# clock-converter.net
KiCad netlist of a schematic drawn in EAGLE
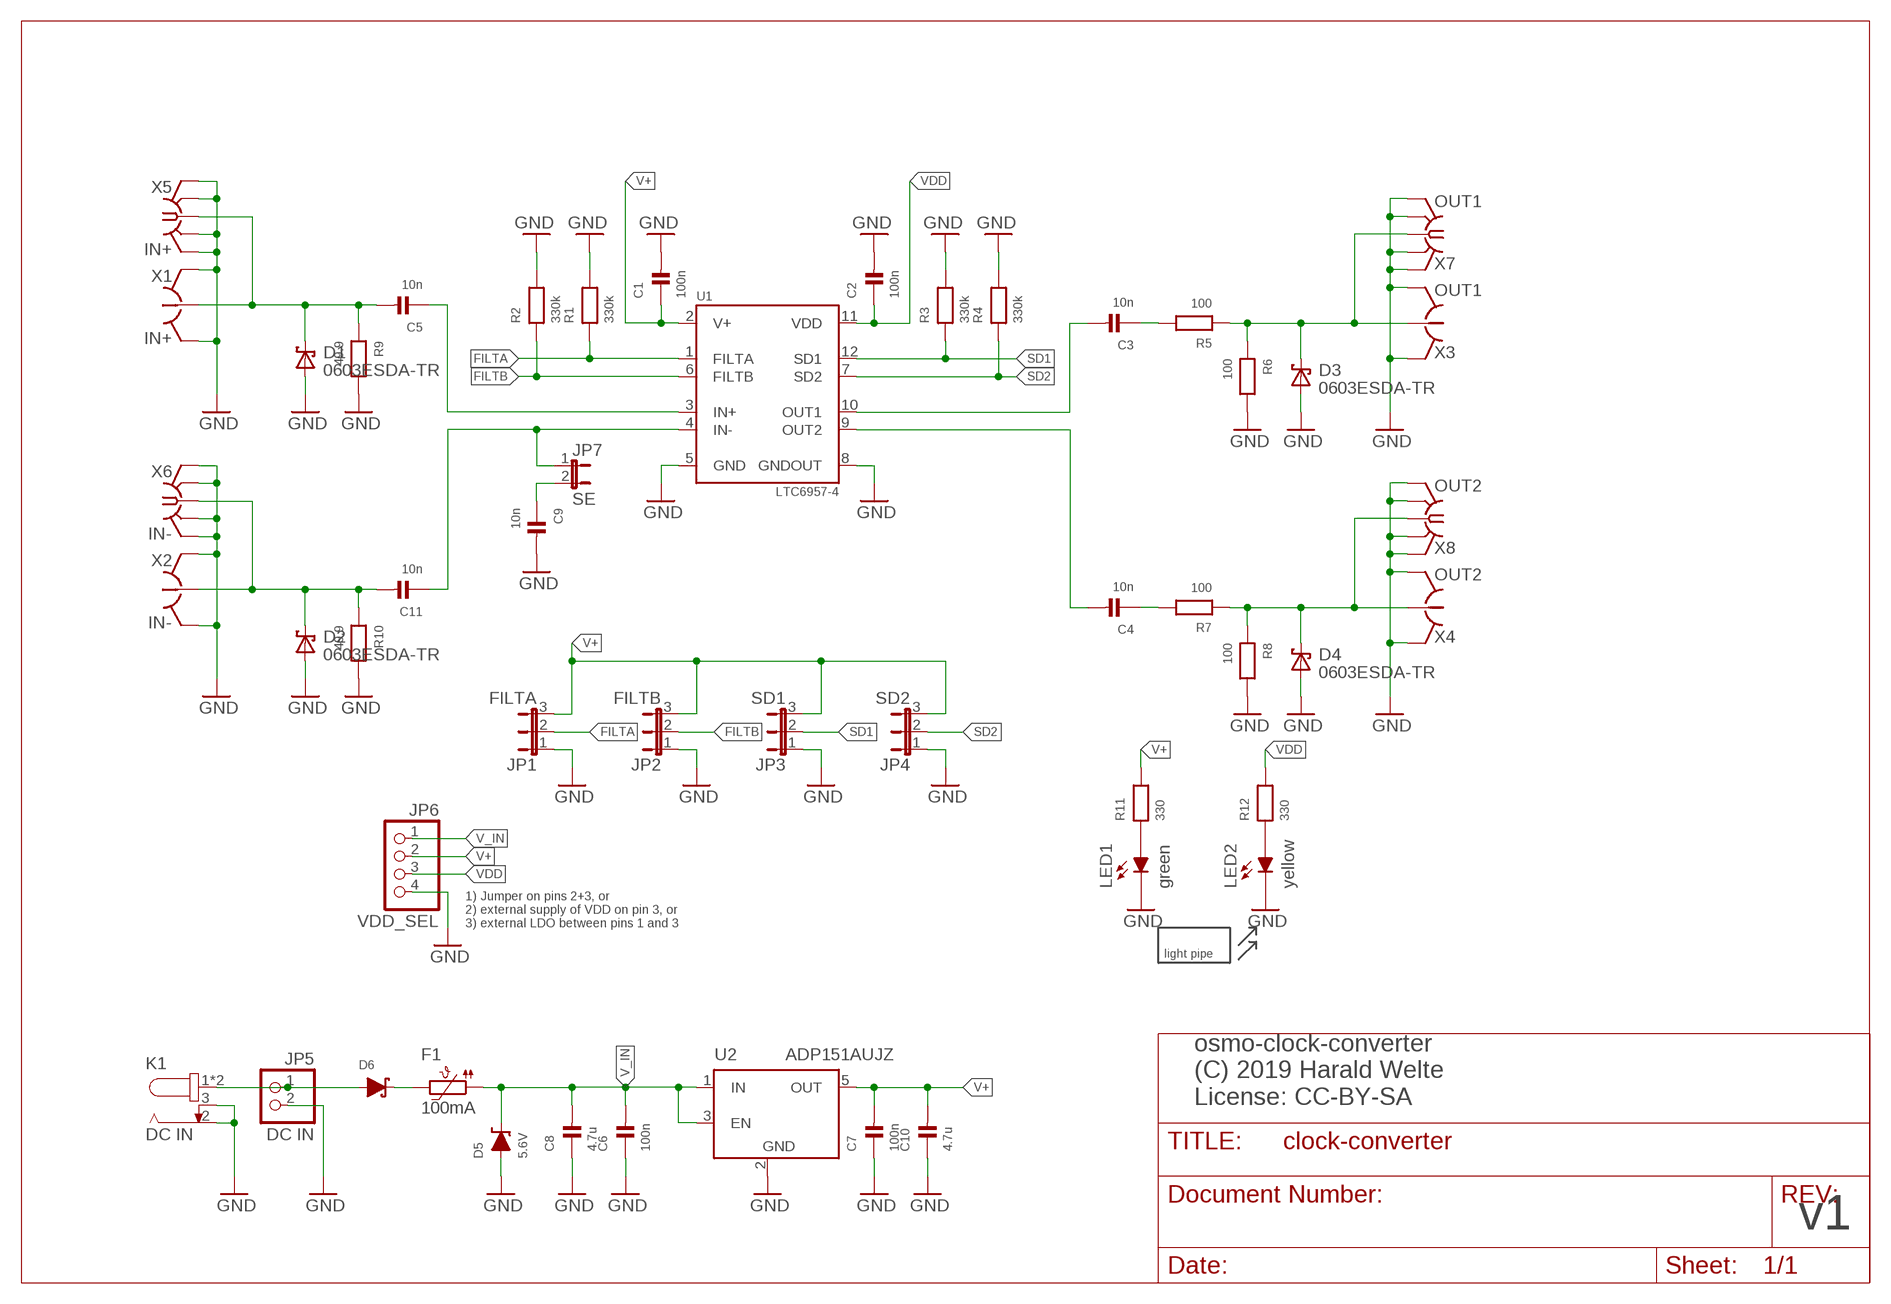
[diagram p0: schematic, sheet 1]

(export (version "E")
  (design (tool "Eeschema 10.0.6"))
  (components
    (comp (ref "C1")
      (value "100n")
      (footprint "eagle-import:_0603")
      (description "CAP CER 0.1UF 16V X7R 0603")
      (fields
        (field (name "MANUFACTURER") "Samsung Electro-Mechanics")
        (field (name "MANUFACTURERPARTNUMBER") "CL10B104KO8NNNC")
      )
      (libsource (lib "eagle-import") (part "CAP_CERAMIC_0603"))
    )
    (comp (ref "C2")
      (value "100n")
      (footprint "eagle-import:_0603")
      (description "CAP CER 0.1UF 16V X7R 0603")
      (fields
        (field (name "MANUFACTURER") "Samsung Electro-Mechanics")
        (field (name "MANUFACTURERPARTNUMBER") "CL10B104KO8NNNC")
      )
      (libsource (lib "eagle-import") (part "CAP_CERAMIC_0603"))
    )
    (comp (ref "C3")
      (value "10n")
      (footprint "eagle-import:_0603")
      (description "CAP CER 10000PF 50V X7R 0603")
      (fields
        (field (name "MANUFACTURER") "KEMET")
        (field (name "MANUFACTURERPARTNUMBER") "C0603C103M5RACTU")
      )
      (libsource (lib "eagle-import") (part "CAP_CERAMIC_0603"))
    )
    (comp (ref "C4")
      (value "10n")
      (footprint "eagle-import:_0603")
      (description "CAP CER 10000PF 50V X7R 0603")
      (fields
        (field (name "MANUFACTURER") "KEMET")
        (field (name "MANUFACTURERPARTNUMBER") "C0603C103M5RACTU")
      )
      (libsource (lib "eagle-import") (part "CAP_CERAMIC_0603"))
    )
    (comp (ref "C5")
      (value "10n")
      (footprint "eagle-import:_0603")
      (description "CAP CER 10000PF 50V X7R 0603")
      (fields
        (field (name "MANUFACTURER") "KEMET")
        (field (name "MANUFACTURERPARTNUMBER") "C0603C103M5RACTU")
      )
      (libsource (lib "eagle-import") (part "CAP_CERAMIC_0603"))
    )
    (comp (ref "C6")
      (value "100n")
      (footprint "eagle-import:_0603")
      (description "CAP CER 0.1UF 16V X7R 0603")
      (fields
        (field (name "MANUFACTURER") "Samsung Electro-Mechanics")
        (field (name "MANUFACTURERPARTNUMBER") "CL10B104KO8NNNC")
      )
      (libsource (lib "eagle-import") (part "CAP_CERAMIC_0603"))
    )
    (comp (ref "C7")
      (value "100n")
      (footprint "eagle-import:_0603")
      (description "CAP CER 0.1UF 16V X7R 0603")
      (fields
        (field (name "MANUFACTURER") "Samsung Electro-Mechanics")
        (field (name "MANUFACTURERPARTNUMBER") "CL10B104KO8NNNC")
      )
      (libsource (lib "eagle-import") (part "CAP_CERAMIC_0603"))
    )
    (comp (ref "C8")
      (value "4.7u")
      (footprint "eagle-import:_0805")
      (description "CAP CER 4.7UF 16V X5R 0805")
      (fields
        (field (name "MANUFACTURER") "Samsung Electro-Mechanics")
        (field (name "MANUFACTURERPARTNUMBER") "CL21A475KOFNNNE")
      )
      (libsource (lib "eagle-import") (part "CAP_CERAMIC_0805"))
    )
    (comp (ref "C9")
      (value "10n")
      (footprint "eagle-import:_0603")
      (description "CAP CER 10000PF 50V X7R 0603")
      (fields
        (field (name "MANUFACTURER") "KEMET")
        (field (name "MANUFACTURERPARTNUMBER") "C0603C103M5RACTU")
      )
      (libsource (lib "eagle-import") (part "CAP_CERAMIC_0603"))
    )
    (comp (ref "C10")
      (value "4.7u")
      (footprint "eagle-import:_0805")
      (description "CAP CER 4.7UF 16V X5R 0805")
      (fields
        (field (name "MANUFACTURER") "Samsung Electro-Mechanics")
        (field (name "MANUFACTURERPARTNUMBER") "CL21A475KOFNNNE")
      )
      (libsource (lib "eagle-import") (part "CAP_CERAMIC_0805"))
    )
    (comp (ref "C11")
      (value "10n")
      (footprint "eagle-import:_0603")
      (description "CAP CER 10000PF 50V X7R 0603")
      (fields
        (field (name "MANUFACTURER") "KEMET")
        (field (name "MANUFACTURERPARTNUMBER") "C0603C103M5RACTU")
      )
      (libsource (lib "eagle-import") (part "CAP_CERAMIC_0603"))
    )
    (comp (ref "D1")
      (value "0603ESDA-TR")
      (footprint "eagle-import:0603")
      (description "SUPPRESSOR ESD 30VDC 0603 SMD")
      (fields
        (field (name "MANUFACTURER") "Eaton - Electronics Division")
        (field (name "MANUFACTURERPARTNUMBER") "0603ESDA2-TR2")
      )
      (libsource (lib "eagle-import") (part "0603ESDA-TR"))
    )
    (comp (ref "D2")
      (value "0603ESDA-TR")
      (footprint "eagle-import:0603")
      (description "SUPPRESSOR ESD 30VDC 0603 SMD")
      (fields
        (field (name "MANUFACTURER") "Eaton - Electronics Division")
        (field (name "MANUFACTURERPARTNUMBER") "0603ESDA2-TR2")
      )
      (libsource (lib "eagle-import") (part "0603ESDA-TR"))
    )
    (comp (ref "D3")
      (value "0603ESDA-TR")
      (footprint "eagle-import:0603")
      (description "SUPPRESSOR ESD 30VDC 0603 SMD")
      (fields
        (field (name "MANUFACTURER") "Eaton - Electronics Division")
        (field (name "MANUFACTURERPARTNUMBER") "0603ESDA2-TR2")
      )
      (libsource (lib "eagle-import") (part "0603ESDA-TR"))
    )
    (comp (ref "D4")
      (value "0603ESDA-TR")
      (footprint "eagle-import:0603")
      (description "SUPPRESSOR ESD 30VDC 0603 SMD")
      (fields
        (field (name "MANUFACTURER") "Eaton - Electronics Division")
        (field (name "MANUFACTURERPARTNUMBER") "0603ESDA2-TR2")
      )
      (libsource (lib "eagle-import") (part "0603ESDA-TR"))
    )
    (comp (ref "D5")
      (value "5.6V")
      (footprint "eagle-import:SMADIODE")
      (description "DIODE ZENER 5.6V 3W DO214AC")
      (fields
        (field (name "MANUFACTURER") "Micro Commercial Co")
        (field (name "MANUFACTURERPARTNUMBER") "3SMAJ5919B-TP")
      )
      (libsource (lib "eagle-import") (part "DIODDE-ZENER-SMA"))
    )
    (comp (ref "D6")
      (value "DIODE-SCHOTTKY-SMA")
      (footprint "eagle-import:SMADIODE")
      (description "DIODE SCHOTTKY 30V 800MA USC")
      (fields
        (field (name "MANUFACTURER") "Toshiba Semiconductor and Storage")
        (field (name "MANUFACTURERPARTNUMBER") "CUS08F30,H3F")
      )
      (libsource (lib "eagle-import") (part "DIODE-SCHOTTKY-SMA"))
    )
    (comp (ref "F1")
      (value "100mA")
      (footprint "eagle-import:1206L")
      (description "PTC RESET FUSE 30V 200MA 1206")
      (fields
        (field (name "MANUFACTURER") "Bel Fuse Inc.")
        (field (name "MANUFACTURERPARTNUMBER") "0ZCJ0020FF2E")
      )
      (libsource (lib "eagle-import") (part "POLYFUSE-1206L"))
    )
    (comp (ref "JP1")
      (value "FILTA")
      (footprint "eagle-import:JP2")
      (description "CONN HEADER VERT 3POS 2.54MM")
      (fields
        (field (name "MANUFACTURER") "Wurth Electronics Inc.")
        (field (name "MANUFACTURERPARTNUMBER") "61300311121")
      )
      (libsource (lib "eagle-import") (part "JP2E"))
    )
    (comp (ref "JP2")
      (value "FILTB")
      (footprint "eagle-import:JP2")
      (description "CONN HEADER VERT 3POS 2.54MM")
      (fields
        (field (name "MANUFACTURER") "Wurth Electronics Inc.")
        (field (name "MANUFACTURERPARTNUMBER") "61300311121")
      )
      (libsource (lib "eagle-import") (part "JP2E"))
    )
    (comp (ref "JP3")
      (value "SD1")
      (footprint "eagle-import:JP2")
      (description "CONN HEADER VERT 3POS 2.54MM")
      (fields
        (field (name "MANUFACTURER") "Wurth Electronics Inc.")
        (field (name "MANUFACTURERPARTNUMBER") "61300311121")
      )
      (libsource (lib "eagle-import") (part "JP2E"))
    )
    (comp (ref "JP4")
      (value "SD2")
      (footprint "eagle-import:JP2")
      (description "CONN HEADER VERT 3POS 2.54MM")
      (fields
        (field (name "MANUFACTURER") "Wurth Electronics Inc.")
        (field (name "MANUFACTURERPARTNUMBER") "61300311121")
      )
      (libsource (lib "eagle-import") (part "JP2E"))
    )
    (comp (ref "JP5")
      (value "DC IN")
      (footprint "eagle-import:1X02")
      (description "CONN HEADER VERT 2POS 2.54MM")
      (fields
        (field (name "MANUFACTURER") "Sullins Connector Solutions")
        (field (name "MANUFACTURERPARTNUMBER") "PREC002SAAN-RC")
      )
      (libsource (lib "eagle-import") (part "PINHD-1X2"))
    )
    (comp (ref "JP6")
      (value "VDD_SEL")
      (footprint "eagle-import:1X04")
      (description "CONN HEADER VERT 4POS 2.54MM")
      (fields
        (field (name "MANUFACTURER") "Sullins Connector Solutions")
        (field (name "MANUFACTURERPARTNUMBER") "PRPC004SAAN-RC")
      )
      (libsource (lib "eagle-import") (part "PINHD-1X4"))
    )
    (comp (ref "JP7")
      (value "SE")
      (footprint "eagle-import:JP1")
      (description "CONN HEADER VERT 2POS 2.54MM")
      (fields
        (field (name "MANUFACTURER") "Sullins Connector Solutions")
        (field (name "MANUFACTURERPARTNUMBER") "PREC002SAAN-RC")
      )
      (libsource (lib "eagle-import") (part "JP1E"))
    )
    (comp (ref "K1")
      (value "DC IN")
      (footprint "eagle-import:694108106102")
      (description "CONN PWR JACK 2.5X5.5MM SOLDER")
      (fields
        (field (name "MANUFACTURER") "Wurth Electronics Inc.")
        (field (name "MANUFACTURERPARTNUMBER") "694108106102")
      )
      (libsource (lib "eagle-import") (part "694108106102"))
    )
    (comp (ref "LED1")
      (value "green")
      (footprint "eagle-import:PLCC2-MIN")
      (description "LED GREEN CLEAR 2PLCC SMD")
      (fields
        (field (name "MANUFACTURER") "OSRAM Opto Semiconductors Inc.")
        (field (name "MANUFACTURERPARTNUMBER") "LG T67F-R1T1-24")
      )
      (libsource (lib "eagle-import") (part "LEDPLCC2-MIN"))
    )
    (comp (ref "LED2")
      (value "yellow")
      (footprint "eagle-import:PLCC2-MIN")
      (description "LED YELLOW CLEAR 2PLCC SMD")
      (fields
        (field (name "MANUFACTURER") "OSRAM Opto Semiconductors Inc.")
        (field (name "MANUFACTURERPARTNUMBER") "LY T676-S1T1-26-Z")
      )
      (libsource (lib "eagle-import") (part "LEDPLCC2-MIN"))
    )
    (comp (ref "M1")
      (value "MENTOR_12701001")
      (footprint "eagle-import:1270.1001")
      (description "NO DESCRIPTION")
      (fields
        (field (name "MANUFACTURER") "UNKNOWN MANUFACTURER")
        (field (name "MANUFACTURERPARTNUMBER") "UNKNOWN MANUFACTURER PART NUMBER")
      )
      (libsource (lib "eagle-import") (part "MENTOR_12701001"))
    )
    (comp (ref "R1")
      (value "330k")
      (footprint "eagle-import:_0603")
      (description "RES 330K OHM 5%% 1/10W 0603")
      (fields
        (field (name "MANUFACTURER") "Stackpole Electronics Inc")
        (field (name "MANUFACTURERPARTNUMBER") "RMCF0603JG330K")
      )
      (libsource (lib "eagle-import") (part "RESISTOR_0603"))
    )
    (comp (ref "R2")
      (value "330k")
      (footprint "eagle-import:_0603")
      (description "RES 330K OHM 5%% 1/10W 0603")
      (fields
        (field (name "MANUFACTURER") "Stackpole Electronics Inc")
        (field (name "MANUFACTURERPARTNUMBER") "RMCF0603JG330K")
      )
      (libsource (lib "eagle-import") (part "RESISTOR_0603"))
    )
    (comp (ref "R3")
      (value "330k")
      (footprint "eagle-import:_0603")
      (description "RES 330K OHM 5%% 1/10W 0603")
      (fields
        (field (name "MANUFACTURER") "Stackpole Electronics Inc")
        (field (name "MANUFACTURERPARTNUMBER") "RMCF0603JG330K")
      )
      (libsource (lib "eagle-import") (part "RESISTOR_0603"))
    )
    (comp (ref "R4")
      (value "330k")
      (footprint "eagle-import:_0603")
      (description "RES 330K OHM 5%% 1/10W 0603")
      (fields
        (field (name "MANUFACTURER") "Stackpole Electronics Inc")
        (field (name "MANUFACTURERPARTNUMBER") "RMCF0603JG330K")
      )
      (libsource (lib "eagle-import") (part "RESISTOR_0603"))
    )
    (comp (ref "R5")
      (value "100")
      (footprint "eagle-import:_0603")
      (description "RES 100 OHM 5%% 1/10W 0603")
      (fields
        (field (name "MANUFACTURER") "Stackpole Electronics Inc")
        (field (name "MANUFACTURERPARTNUMBER") "RMCF0603JT100R")
      )
      (libsource (lib "eagle-import") (part "RESISTOR_0603"))
    )
    (comp (ref "R6")
      (value "100")
      (footprint "eagle-import:_0603")
      (description "RES 100 OHM 5%% 1/10W 0603")
      (fields
        (field (name "MANUFACTURER") "Stackpole Electronics Inc")
        (field (name "MANUFACTURERPARTNUMBER") "RMCF0603JT100R")
      )
      (libsource (lib "eagle-import") (part "RESISTOR_0603"))
    )
    (comp (ref "R7")
      (value "100")
      (footprint "eagle-import:_0603")
      (description "RES 100 OHM 5%% 1/10W 0603")
      (fields
        (field (name "MANUFACTURER") "Stackpole Electronics Inc")
        (field (name "MANUFACTURERPARTNUMBER") "RMCF0603JT100R")
      )
      (libsource (lib "eagle-import") (part "RESISTOR_0603"))
    )
    (comp (ref "R8")
      (value "100")
      (footprint "eagle-import:_0603")
      (description "RES 100 OHM 5%% 1/10W 0603")
      (fields
        (field (name "MANUFACTURER") "Stackpole Electronics Inc")
        (field (name "MANUFACTURERPARTNUMBER") "RMCF0603JT100R")
      )
      (libsource (lib "eagle-import") (part "RESISTOR_0603"))
    )
    (comp (ref "R9")
      (value "49.9")
      (footprint "eagle-import:_0603")
      (description "RES 49.9 OHM 1%% 1/10W 0603")
      (fields
        (field (name "MANUFACTURER") "Stackpole Electronics Inc")
        (field (name "MANUFACTURERPARTNUMBER") "RMCF0603FT49R9")
      )
      (libsource (lib "eagle-import") (part "RESISTOR_0603"))
    )
    (comp (ref "R10")
      (value "49.9")
      (footprint "eagle-import:_0603")
      (description "RES 49.9 OHM 1%% 1/10W 0603")
      (fields
        (field (name "MANUFACTURER") "Stackpole Electronics Inc")
        (field (name "MANUFACTURERPARTNUMBER") "RMCF0603FT49R9")
      )
      (libsource (lib "eagle-import") (part "RESISTOR_0603"))
    )
    (comp (ref "R11")
      (value "330")
      (footprint "eagle-import:_0603")
      (description "RES 330 OHM 5%% 1/10W 0603")
      (fields
        (field (name "MANUFACTURER") "Stackpole Electronics Inc")
        (field (name "MANUFACTURERPARTNUMBER") "RMCF0603JT330R")
      )
      (libsource (lib "eagle-import") (part "RESISTOR_0603"))
    )
    (comp (ref "R12")
      (value "330")
      (footprint "eagle-import:_0603")
      (description "RES 330 OHM 5%% 1/10W 0603")
      (fields
        (field (name "MANUFACTURER") "Stackpole Electronics Inc")
        (field (name "MANUFACTURERPARTNUMBER") "RMCF0603JT330R")
      )
      (libsource (lib "eagle-import") (part "RESISTOR_0603"))
    )
    (comp (ref "U1")
      (value "LTC6957-4")
      (footprint "eagle-import:MSOP12")
      (description "IC CLK BUFFER DVR 1:2 12MSOP")
      (fields
        (field (name "MANUFACTURER") "Linear Technology/Analog Devices")
        (field (name "MANUFACTURERPARTNUMBER") "LTC6957IMS-3#PBF")
      )
      (libsource (lib "eagle-import") (part "LTC6957-3/4-HMS"))
    )
    (comp (ref "U2")
      (value "ADP151AUJZ")
      (footprint "eagle-import:SOT23L")
      (description "IC REG LINEAR 3V 200MA TSOT5")
      (fields
        (field (name "MANUFACTURER") "Analog Devices Inc.")
        (field (name "MANUFACTURERPARTNUMBER") "ADP151AUJZ-3.0-R7")
      )
      (libsource (lib "eagle-import") (part "LDO_FIXED_EN-ADP151AUJZ"))
    )
    (comp (ref "X1")
      (value "IN+")
      (footprint "eagle-import:HRS_UFL")
      (description "CONN U.FL RCPT STR 50 OHM SMD")
      (fields
        (field (name "MANUFACTURER") "Hirose Electric Co Ltd")
        (field (name "MANUFACTURERPARTNUMBER") "U.FL-R-SMT(10)")
      )
      (libsource (lib "eagle-import") (part "HRS_UFL"))
    )
    (comp (ref "X2")
      (value "IN-")
      (footprint "eagle-import:HRS_UFL")
      (description "CONN U.FL RCPT STR 50 OHM SMD")
      (fields
        (field (name "MANUFACTURER") "Hirose Electric Co Ltd")
        (field (name "MANUFACTURERPARTNUMBER") "U.FL-R-SMT(10)")
      )
      (libsource (lib "eagle-import") (part "HRS_UFL"))
    )
    (comp (ref "X3")
      (value "OUT1")
      (footprint "eagle-import:HRS_UFL")
      (description "CONN U.FL RCPT STR 50 OHM SMD")
      (fields
        (field (name "MANUFACTURER") "Hirose Electric Co Ltd")
        (field (name "MANUFACTURERPARTNUMBER") "U.FL-R-SMT(10)")
      )
      (libsource (lib "eagle-import") (part "HRS_UFL"))
    )
    (comp (ref "X4")
      (value "OUT2")
      (footprint "eagle-import:HRS_UFL")
      (description "CONN U.FL RCPT STR 50 OHM SMD")
      (fields
        (field (name "MANUFACTURER") "Hirose Electric Co Ltd")
        (field (name "MANUFACTURERPARTNUMBER") "U.FL-R-SMT(10)")
      )
      (libsource (lib "eagle-import") (part "HRS_UFL"))
    )
    (comp (ref "X5")
      (value "IN+")
      (footprint "eagle-import:SMA-F-S-TH")
      (description "CONN SMA JACK R/A 50 OHM PCB")
      (fields
        (field (name "MANUFACTURER") "TE Connectivity AMP Connectors")
        (field (name "MANUFACTURERPARTNUMBER") "619540-1")
      )
      (libsource (lib "eagle-import") (part "SMA-F-S-TH"))
    )
    (comp (ref "X6")
      (value "IN-")
      (footprint "eagle-import:SMA-F-S-TH")
      (description "CONN SMA JACK R/A 50 OHM PCB")
      (fields
        (field (name "MANUFACTURER") "TE Connectivity AMP Connectors")
        (field (name "MANUFACTURERPARTNUMBER") "619540-1")
      )
      (libsource (lib "eagle-import") (part "SMA-F-S-TH"))
    )
    (comp (ref "X7")
      (value "OUT1")
      (footprint "eagle-import:SMA-F-S-TH")
      (description "CONN SMA JACK R/A 50 OHM PCB")
      (fields
        (field (name "MANUFACTURER") "TE Connectivity AMP Connectors")
        (field (name "MANUFACTURERPARTNUMBER") "619540-1")
      )
      (libsource (lib "eagle-import") (part "SMA-F-S-TH"))
    )
    (comp (ref "X8")
      (value "OUT2")
      (footprint "eagle-import:SMA-F-S-TH")
      (description "CONN SMA JACK R/A 50 OHM PCB")
      (fields
        (field (name "MANUFACTURER") "TE Connectivity AMP Connectors")
        (field (name "MANUFACTURERPARTNUMBER") "619540-1")
      )
      (libsource (lib "eagle-import") (part "SMA-F-S-TH"))
    )
  )
  (nets
    (net (code "1") (name "FILTA") (class "Default")
      (node (ref "JP1") (pin "2") (pinfunction "2_2") (pintype "passive"))
      (node (ref "R1") (pin "1") (pinfunction "1_1") (pintype "passive"))
      (node (ref "U1") (pin "1") (pinfunction "FILTA_1") (pintype "input"))
    )
    (net (code "2") (name "FILTB") (class "Default")
      (node (ref "JP2") (pin "2") (pinfunction "2_2") (pintype "passive"))
      (node (ref "R2") (pin "1") (pinfunction "1_1") (pintype "passive"))
      (node (ref "U1") (pin "6") (pinfunction "FILTB_6") (pintype "input"))
    )
    (net (code "3") (name "GND") (class "Default")
      (node (ref "C1") (pin "2") (pinfunction "2_2") (pintype "passive"))
      (node (ref "C10") (pin "1") (pinfunction "1_1") (pintype "passive"))
      (node (ref "C2") (pin "2") (pinfunction "2_2") (pintype "passive"))
      (node (ref "C6") (pin "1") (pinfunction "1_1") (pintype "passive"))
      (node (ref "C7") (pin "1") (pinfunction "1_1") (pintype "passive"))
      (node (ref "C8") (pin "1") (pinfunction "1_1") (pintype "passive"))
      (node (ref "C9") (pin "2") (pinfunction "2_2") (pintype "passive"))
      (node (ref "D1") (pin "1") (pinfunction "A_1") (pintype "passive"))
      (node (ref "D2") (pin "1") (pinfunction "A_1") (pintype "passive"))
      (node (ref "D3") (pin "1") (pinfunction "A_1") (pintype "passive"))
      (node (ref "D4") (pin "1") (pinfunction "A_1") (pintype "passive"))
      (node (ref "D5") (pin "A") (pinfunction "A_A") (pintype "passive"))
      (node (ref "JP1") (pin "1") (pinfunction "1_1") (pintype "passive"))
      (node (ref "JP2") (pin "1") (pinfunction "1_1") (pintype "passive"))
      (node (ref "JP3") (pin "1") (pinfunction "1_1") (pintype "passive"))
      (node (ref "JP4") (pin "1") (pinfunction "1_1") (pintype "passive"))
      (node (ref "JP5") (pin "2") (pinfunction "2_2") (pintype "passive"))
      (node (ref "JP6") (pin "4") (pinfunction "4_4") (pintype "passive"))
      (node (ref "K1") (pin "2") (pinfunction "2_2") (pintype "passive"))
      (node (ref "K1") (pin "3") (pinfunction "3_3") (pintype "passive"))
      (node (ref "LED1") (pin "K") (pinfunction "C_K") (pintype "passive"))
      (node (ref "LED2") (pin "K") (pinfunction "C_K") (pintype "passive"))
      (node (ref "R1") (pin "2") (pinfunction "2_2") (pintype "passive"))
      (node (ref "R10") (pin "2") (pinfunction "2_2") (pintype "passive"))
      (node (ref "R2") (pin "2") (pinfunction "2_2") (pintype "passive"))
      (node (ref "R3") (pin "2") (pinfunction "2_2") (pintype "passive"))
      (node (ref "R4") (pin "2") (pinfunction "2_2") (pintype "passive"))
      (node (ref "R6") (pin "2") (pinfunction "2_2") (pintype "passive"))
      (node (ref "R8") (pin "2") (pinfunction "2_2") (pintype "passive"))
      (node (ref "R9") (pin "2") (pinfunction "2_2") (pintype "passive"))
      (node (ref "U1") (pin "5") (pinfunction "GND_5") (pintype "passive"))
      (node (ref "U1") (pin "8") (pinfunction "GNDOUT_8") (pintype "passive"))
      (node (ref "U2") (pin "2") (pinfunction "GND_2") (pintype "power_in"))
      (node (ref "X1") (pin "GND@1") (pinfunction "GND_GND@1") (pintype "power_in"))
      (node (ref "X1") (pin "GND@2") (pinfunction "GND_GND@2") (pintype "power_in"))
      (node (ref "X2") (pin "GND@1") (pinfunction "GND_GND@1") (pintype "power_in"))
      (node (ref "X2") (pin "GND@2") (pinfunction "GND_GND@2") (pintype "power_in"))
      (node (ref "X3") (pin "GND@1") (pinfunction "GND_GND@1") (pintype "power_in"))
      (node (ref "X3") (pin "GND@2") (pinfunction "GND_GND@2") (pintype "power_in"))
      (node (ref "X4") (pin "GND@1") (pinfunction "GND_GND@1") (pintype "power_in"))
      (node (ref "X4") (pin "GND@2") (pinfunction "GND_GND@2") (pintype "power_in"))
      (node (ref "X5") (pin "G1") (pinfunction "GND_G1") (pintype "power_in"))
      (node (ref "X5") (pin "G2") (pinfunction "GND_G2") (pintype "power_in"))
      (node (ref "X5") (pin "G3") (pinfunction "GND_G3") (pintype "power_in"))
      (node (ref "X5") (pin "G4") (pinfunction "GND_G4") (pintype "power_in"))
      (node (ref "X6") (pin "G1") (pinfunction "GND_G1") (pintype "power_in"))
      (node (ref "X6") (pin "G2") (pinfunction "GND_G2") (pintype "power_in"))
      (node (ref "X6") (pin "G3") (pinfunction "GND_G3") (pintype "power_in"))
      (node (ref "X6") (pin "G4") (pinfunction "GND_G4") (pintype "power_in"))
      (node (ref "X7") (pin "G1") (pinfunction "GND_G1") (pintype "power_in"))
      (node (ref "X7") (pin "G2") (pinfunction "GND_G2") (pintype "power_in"))
      (node (ref "X7") (pin "G3") (pinfunction "GND_G3") (pintype "power_in"))
      (node (ref "X7") (pin "G4") (pinfunction "GND_G4") (pintype "power_in"))
      (node (ref "X8") (pin "G1") (pinfunction "GND_G1") (pintype "power_in"))
      (node (ref "X8") (pin "G2") (pinfunction "GND_G2") (pintype "power_in"))
      (node (ref "X8") (pin "G3") (pinfunction "GND_G3") (pintype "power_in"))
      (node (ref "X8") (pin "G4") (pinfunction "GND_G4") (pintype "power_in"))
    )
    (net (code "4") (name "Net-(C3-Pad1)") (class "Default")
      (node (ref "C3") (pin "1") (pinfunction "1_1") (pintype "passive"))
      (node (ref "R5") (pin "2") (pinfunction "2_2") (pintype "passive"))
    )
    (net (code "5") (name "Net-(C4-Pad1)") (class "Default")
      (node (ref "C4") (pin "1") (pinfunction "1_1") (pintype "passive"))
      (node (ref "R7") (pin "2") (pinfunction "2_2") (pintype "passive"))
    )
    (net (code "6") (name "Net-(C9-Pad1)") (class "Default")
      (node (ref "C9") (pin "1") (pinfunction "1_1") (pintype "passive"))
      (node (ref "JP7") (pin "2") (pinfunction "2_2") (pintype "passive"))
    )
    (net (code "7") (name "Net-(D1-K)") (class "Default")
      (node (ref "C5") (pin "2") (pinfunction "2_2") (pintype "passive"))
      (node (ref "D1") (pin "2") (pinfunction "K_2") (pintype "passive"))
      (node (ref "R9") (pin "1") (pinfunction "1_1") (pintype "passive"))
      (node (ref "X1") (pin "SIG") (pinfunction "1_SIG") (pintype "passive"))
      (node (ref "X5") (pin "C") (pinfunction "1_C") (pintype "passive"))
    )
    (net (code "8") (name "Net-(D2-K)") (class "Default")
      (node (ref "C11") (pin "2") (pinfunction "2_2") (pintype "passive"))
      (node (ref "D2") (pin "2") (pinfunction "K_2") (pintype "passive"))
      (node (ref "R10") (pin "1") (pinfunction "1_1") (pintype "passive"))
      (node (ref "X2") (pin "SIG") (pinfunction "1_SIG") (pintype "passive"))
      (node (ref "X6") (pin "C") (pinfunction "1_C") (pintype "passive"))
    )
    (net (code "9") (name "Net-(D3-K)") (class "Default")
      (node (ref "D3") (pin "2") (pinfunction "K_2") (pintype "passive"))
      (node (ref "R5") (pin "1") (pinfunction "1_1") (pintype "passive"))
      (node (ref "R6") (pin "1") (pinfunction "1_1") (pintype "passive"))
      (node (ref "X3") (pin "SIG") (pinfunction "1_SIG") (pintype "passive"))
      (node (ref "X7") (pin "C") (pinfunction "1_C") (pintype "passive"))
    )
    (net (code "10") (name "Net-(D4-K)") (class "Default")
      (node (ref "D4") (pin "2") (pinfunction "K_2") (pintype "passive"))
      (node (ref "R7") (pin "1") (pinfunction "1_1") (pintype "passive"))
      (node (ref "R8") (pin "1") (pinfunction "1_1") (pintype "passive"))
      (node (ref "X4") (pin "SIG") (pinfunction "1_SIG") (pintype "passive"))
      (node (ref "X8") (pin "C") (pinfunction "1_C") (pintype "passive"))
    )
    (net (code "11") (name "Net-(D6-PadA)") (class "Default")
      (node (ref "D6") (pin "A") (pinfunction "A_A") (pintype "passive"))
      (node (ref "JP5") (pin "1") (pinfunction "1_1") (pintype "passive"))
      (node (ref "K1") (pin "1") (pinfunction "1_1") (pintype "passive"))
      (node (ref "K1") (pin "1-1") (pinfunction "1_1-1") (pintype "passive"))
    )
    (net (code "12") (name "Net-(D6-PadC)") (class "Default")
      (node (ref "D6") (pin "C") (pinfunction "C_C") (pintype "passive"))
      (node (ref "F1") (pin "2") (pinfunction "2_2") (pintype "passive"))
    )
    (net (code "13") (name "Net-(LED1-PadA)") (class "Default")
      (node (ref "LED1") (pin "A") (pinfunction "A_A") (pintype "passive"))
      (node (ref "R11") (pin "1") (pinfunction "1_1") (pintype "passive"))
    )
    (net (code "14") (name "Net-(LED2-PadA)") (class "Default")
      (node (ref "LED2") (pin "A") (pinfunction "A_A") (pintype "passive"))
      (node (ref "R12") (pin "1") (pinfunction "1_1") (pintype "passive"))
    )
    (net (code "15") (name "Net-(U1-IN+)") (class "Default")
      (node (ref "C5") (pin "1") (pinfunction "1_1") (pintype "passive"))
      (node (ref "U1") (pin "3") (pinfunction "IN+_3") (pintype "input"))
    )
    (net (code "16") (name "Net-(U1-IN-)") (class "Default")
      (node (ref "C11") (pin "1") (pinfunction "1_1") (pintype "passive"))
      (node (ref "JP7") (pin "1") (pinfunction "1_1") (pintype "passive"))
      (node (ref "U1") (pin "4") (pinfunction "IN-_4") (pintype "input"))
    )
    (net (code "17") (name "Net-(U1-OUT1)") (class "Default")
      (node (ref "C3") (pin "2") (pinfunction "2_2") (pintype "passive"))
      (node (ref "U1") (pin "10") (pinfunction "OUT1_10") (pintype "output"))
    )
    (net (code "18") (name "Net-(U1-OUT2)") (class "Default")
      (node (ref "C4") (pin "2") (pinfunction "2_2") (pintype "passive"))
      (node (ref "U1") (pin "9") (pinfunction "OUT2_9") (pintype "output"))
    )
    (net (code "19") (name "SD1") (class "Default")
      (node (ref "JP3") (pin "2") (pinfunction "2_2") (pintype "passive"))
      (node (ref "R3") (pin "1") (pinfunction "1_1") (pintype "passive"))
      (node (ref "U1") (pin "12") (pinfunction "SD1_12") (pintype "input"))
    )
    (net (code "20") (name "SD2") (class "Default")
      (node (ref "JP4") (pin "2") (pinfunction "2_2") (pintype "passive"))
      (node (ref "R4") (pin "1") (pinfunction "1_1") (pintype "passive"))
      (node (ref "U1") (pin "7") (pinfunction "SD2_7") (pintype "input"))
    )
    (net (code "21") (name "V+") (class "Default")
      (node (ref "C1") (pin "1") (pinfunction "1_1") (pintype "passive"))
      (node (ref "C10") (pin "2") (pinfunction "2_2") (pintype "passive"))
      (node (ref "C7") (pin "2") (pinfunction "2_2") (pintype "passive"))
      (node (ref "JP1") (pin "3") (pinfunction "3_3") (pintype "passive"))
      (node (ref "JP2") (pin "3") (pinfunction "3_3") (pintype "passive"))
      (node (ref "JP3") (pin "3") (pinfunction "3_3") (pintype "passive"))
      (node (ref "JP4") (pin "3") (pinfunction "3_3") (pintype "passive"))
      (node (ref "JP6") (pin "2") (pinfunction "2_2") (pintype "passive"))
      (node (ref "R11") (pin "2") (pinfunction "2_2") (pintype "passive"))
      (node (ref "U1") (pin "2") (pinfunction "V+_2") (pintype "passive"))
      (node (ref "U2") (pin "5") (pinfunction "OUT_5") (pintype "passive"))
    )
    (net (code "22") (name "VDD") (class "Default")
      (node (ref "C2") (pin "1") (pinfunction "1_1") (pintype "passive"))
      (node (ref "JP6") (pin "3") (pinfunction "3_3") (pintype "passive"))
      (node (ref "R12") (pin "2") (pinfunction "2_2") (pintype "passive"))
      (node (ref "U1") (pin "11") (pinfunction "VDD_11") (pintype "passive"))
    )
    (net (code "23") (name "V_IN") (class "Default")
      (node (ref "C6") (pin "2") (pinfunction "2_2") (pintype "passive"))
      (node (ref "C8") (pin "2") (pinfunction "2_2") (pintype "passive"))
      (node (ref "D5") (pin "C") (pinfunction "C_C") (pintype "passive"))
      (node (ref "F1") (pin "1") (pinfunction "1_1") (pintype "passive"))
      (node (ref "JP6") (pin "1") (pinfunction "1_1") (pintype "passive"))
      (node (ref "U2") (pin "1") (pinfunction "IN_1") (pintype "input"))
      (node (ref "U2") (pin "3") (pinfunction "EN_3") (pintype "input"))
    )
  )
)
